# Pyro-Other.net
KiCad netlist of a schematic drawn in Altium Designer
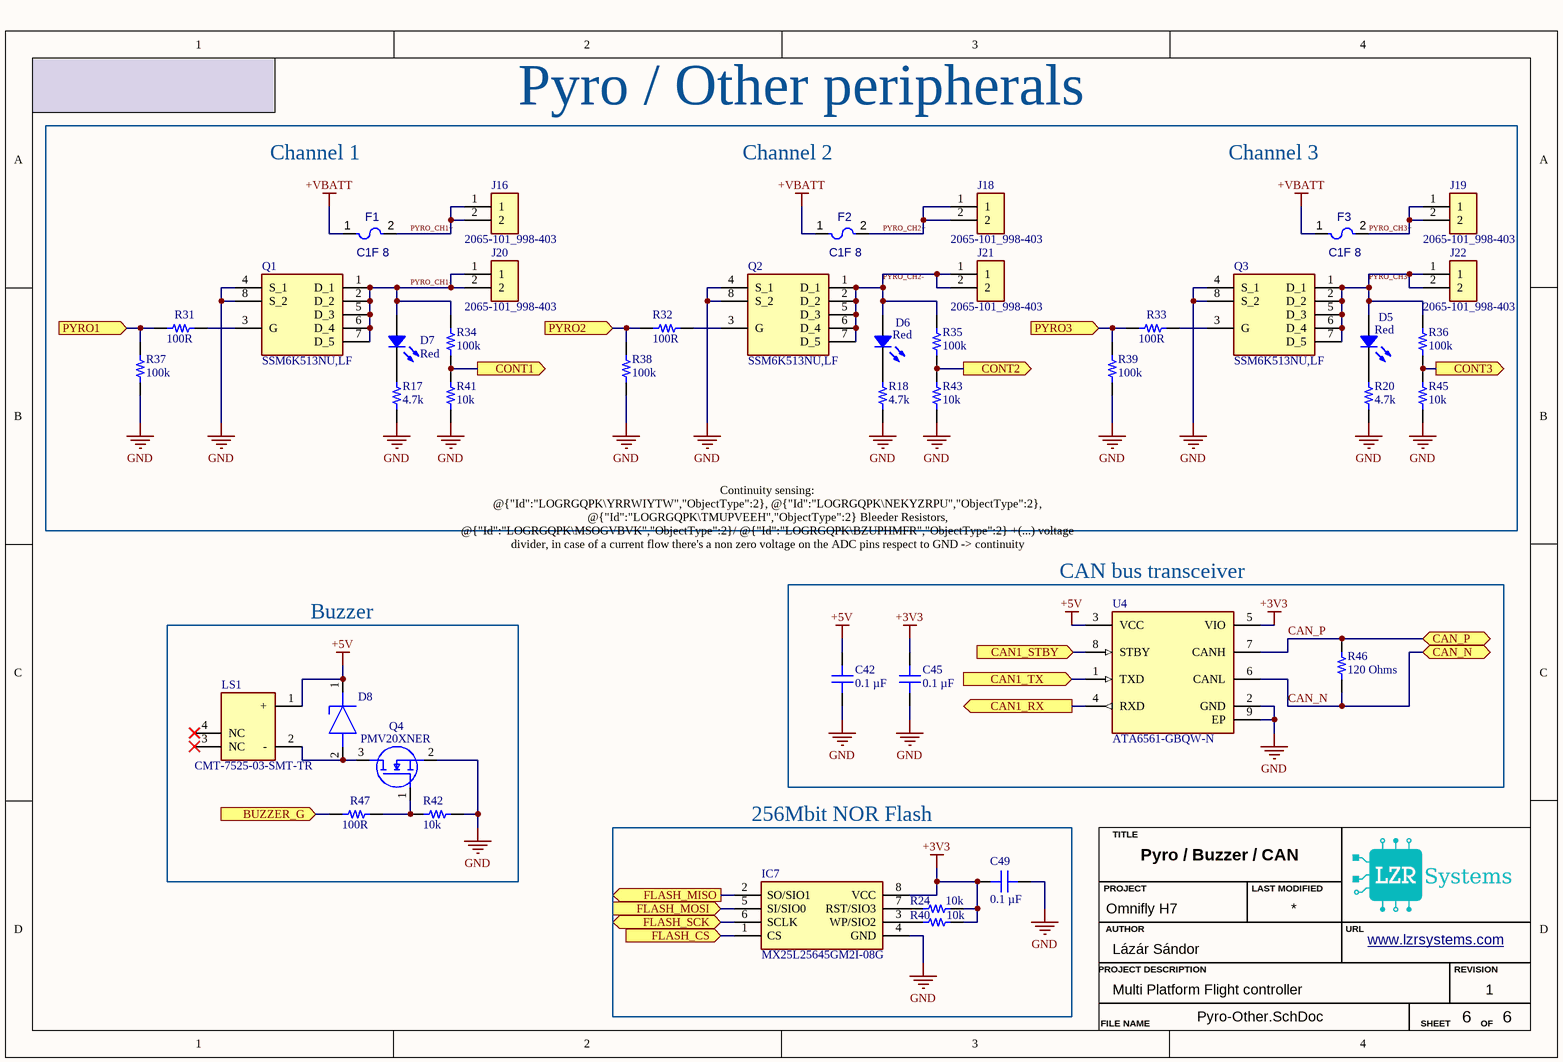
[diagram p0: Pyro-Other.SchDoc]

(export (version "E")
  (design (tool "Eeschema 10.0.6"))
  (components
    (comp (ref "C42")
      (value "0.1 µF")
      (footprint "MURATA GCM155 0402_1005")
      (description "CAP CER 0.1UF 50V X7R 0402")
      (fields
        (field (name "PART NUMBER") "GCM155R71H104ME02D")
        (field (name "CAPACITANCE") "0.1 µF")
        (field (name "MANUFACTURER") "Murata Electronics")
      )
      (libsource (lib "Celestial Altium Library - altium_library") (part "Capacitor"))
    )
    (comp (ref "C45")
      (value "0.1 µF")
      (footprint "MURATA GCM155 0402_1005")
      (description "CAP CER 0.1UF 50V X7R 0402")
      (fields
        (field (name "PART NUMBER") "GCM155R71H104ME02D")
        (field (name "CAPACITANCE") "0.1 µF")
        (field (name "MANUFACTURER") "Murata Electronics")
      )
      (libsource (lib "Celestial Altium Library - altium_library") (part "Capacitor"))
    )
    (comp (ref "C49")
      (value "0.1 µF")
      (footprint "MURATA GCM155 0402_1005")
      (description "CAP CER 0.1UF 50V X7R 0402")
      (fields
        (field (name "PART NUMBER") "GCM155R71H104ME02D")
        (field (name "CAPACITANCE") "0.1 µF")
        (field (name "MANUFACTURER") "Murata Electronics")
      )
      (libsource (lib "Celestial Altium Library - altium_library") (part "Capacitor"))
    )
    (comp (ref "D5")
      (value "Red")
      (footprint "LED 0402_1005 RED")
      (description "LED RED CLEAR 0402 SMD")
      (fields (field (name "PART NUMBER") "SM0402RC") (field (name "MANUFACTURER") "Bivar Inc."))
      (libsource (lib "Celestial Altium Library - altium_library") (part "LED"))
    )
    (comp (ref "D6")
      (value "Red")
      (footprint "LED 0402_1005 RED")
      (description "LED RED CLEAR 0402 SMD")
      (fields (field (name "PART NUMBER") "SM0402RC") (field (name "MANUFACTURER") "Bivar Inc."))
      (libsource (lib "Celestial Altium Library - altium_library") (part "LED"))
    )
    (comp (ref "D7")
      (value "Red")
      (footprint "LED 0402_1005 RED")
      (description "LED RED CLEAR 0402 SMD")
      (fields (field (name "PART NUMBER") "SM0402RC") (field (name "MANUFACTURER") "Bivar Inc."))
      (libsource (lib "Celestial Altium Library - altium_library") (part "LED"))
    )
    (comp (ref "D8")
      (value "PESD24VS1UA")
      (footprint "SamacSys:SOD2512X110N")
      (description "Diode ESD (Uni-directional)")
      (fields
        (field (name "MANUFACTURER_PART_NUMBER") "PESD24VS1UA,115")
        (field (name "MOUSER PART NUMBER") "771-PESD24VS1UA115")
      )
      (libsource (lib "*") (part "PESD24VS1UA,115"))
    )
    (comp (ref "F1")
      (value "C1F 8")
      (footprint "FP-3216FF-IPC_A")
      (description "Fuse Chip Fast Acting 10A 24V SMD Solder Pad 1206 T/R CSA/UL/cULus")
      (libsource (lib "Sandor Lazar") (part "FUSE-2"))
    )
    (comp (ref "F2")
      (value "C1F 8")
      (footprint "FP-3216FF-IPC_A")
      (description "Fuse Chip Fast Acting 10A 24V SMD Solder Pad 1206 T/R CSA/UL/cULus")
      (libsource (lib "Sandor Lazar") (part "FUSE-2"))
    )
    (comp (ref "F3")
      (value "C1F 8")
      (footprint "FP-3216FF-IPC_A")
      (description "Fuse Chip Fast Acting 10A 24V SMD Solder Pad 1206 T/R CSA/UL/cULus")
      (libsource (lib "Sandor Lazar") (part "FUSE-2"))
    )
    (comp (ref "IC7")
      (value "MX25L25645GM2I-08G")
      (footprint "SamacSys:SOIC127P790X216-8N")
      (description "Integrated Circuit")
      (libsource (lib "SamacSys") (part "MX25L25645GM2I-08G"))
    )
    (comp (ref "J16")
      (value "2065-101_998-403")
      (footprint "SamacSys:2065101998403")
      (description "Connector")
      (fields (field (name "MANUFACTURER_PART_NUMBER") "2065-101/998-403"))
      (libsource (lib "SamacSys") (part "2065-101_998-403"))
    )
    (comp (ref "J18")
      (value "2065-101_998-403")
      (footprint "SamacSys:2065101998403")
      (description "Connector")
      (fields (field (name "MANUFACTURER_PART_NUMBER") "2065-101/998-403"))
      (libsource (lib "SamacSys") (part "2065-101_998-403"))
    )
    (comp (ref "J19")
      (value "2065-101_998-403")
      (footprint "SamacSys:2065101998403")
      (description "Connector")
      (fields (field (name "MANUFACTURER_PART_NUMBER") "2065-101/998-403"))
      (libsource (lib "SamacSys") (part "2065-101_998-403"))
    )
    (comp (ref "J20")
      (value "2065-101_998-403")
      (footprint "SamacSys:2065101998403")
      (description "Connector")
      (fields (field (name "MANUFACTURER_PART_NUMBER") "2065-101/998-403"))
      (libsource (lib "SamacSys") (part "2065-101_998-403"))
    )
    (comp (ref "J21")
      (value "2065-101_998-403")
      (footprint "SamacSys:2065101998403")
      (description "Connector")
      (fields (field (name "MANUFACTURER_PART_NUMBER") "2065-101/998-403"))
      (libsource (lib "SamacSys") (part "2065-101_998-403"))
    )
    (comp (ref "J22")
      (value "2065-101_998-403")
      (footprint "SamacSys:2065101998403")
      (description "Connector")
      (fields (field (name "MANUFACTURER_PART_NUMBER") "2065-101/998-403"))
      (libsource (lib "SamacSys") (part "2065-101_998-403"))
    )
    (comp (ref "LS1")
      (value "CMT-7525-03-SMT-TR")
      (footprint "SamacSys:CMT752503SMTTR")
      (description "CMT-7525-03-SMT-TR - 7.5 mm")
      (fields (field (name "MOUSER PART NUMBER") "179-CMT-7525-03SMTTR"))
      (libsource (lib "SamacSys") (part "CMT-7525-03-SMT-TR"))
    )
    (comp (ref "Q1")
      (value "SSM6K513NU,LF")
      (footprint "SamacSys:SSM6K513NULF")
      (description "MOSFET (N-Channel)")
      (fields (field (name "MOUSER PART NUMBER") "757-SSM6K513NULF"))
      (libsource (lib "SamacSys") (part "SSM6K513NU,LF"))
    )
    (comp (ref "Q2")
      (value "SSM6K513NU,LF")
      (footprint "SamacSys:SSM6K513NULF")
      (description "MOSFET (N-Channel)")
      (fields (field (name "MOUSER PART NUMBER") "757-SSM6K513NULF"))
      (libsource (lib "SamacSys") (part "SSM6K513NU,LF"))
    )
    (comp (ref "Q3")
      (value "SSM6K513NU,LF")
      (footprint "SamacSys:SSM6K513NULF")
      (description "MOSFET (N-Channel)")
      (fields (field (name "MOUSER PART NUMBER") "757-SSM6K513NULF"))
      (libsource (lib "SamacSys") (part "SSM6K513NU,LF"))
    )
    (comp (ref "Q4")
      (value "PMV20XNER")
      (footprint "SamacSys:SOT95P230X110-3N")
      (description "MOSFET (N-Channel)")
      (fields (field (name "MOUSER PART NUMBER") "771-PMV20XNER"))
      (libsource (lib "SamacSys") (part "PMV20XNER"))
    )
    (comp (ref "R17")
      (value "4.7k")
      (footprint "YAGEO RES 0402_1005")
      (description "RES 4.7K OHM 1% 1/8W 0402")
      (fields (field (name "PART NUMBER") "AC0402FR-7W4K7L") (field (name "MANUFACTURER") "Yageo"))
      (libsource (lib "Celestial Altium Library - altium_library") (part "Resistor"))
    )
    (comp (ref "R18")
      (value "4.7k")
      (footprint "YAGEO RES 0402_1005")
      (description "RES 4.7K OHM 1% 1/8W 0402")
      (fields (field (name "PART NUMBER") "AC0402FR-7W4K7L") (field (name "MANUFACTURER") "Yageo"))
      (libsource (lib "Celestial Altium Library - altium_library") (part "Resistor"))
    )
    (comp (ref "R20")
      (value "4.7k")
      (footprint "YAGEO RES 0402_1005")
      (description "RES 4.7K OHM 1% 1/8W 0402")
      (fields (field (name "PART NUMBER") "AC0402FR-7W4K7L") (field (name "MANUFACTURER") "Yageo"))
      (libsource (lib "Celestial Altium Library - altium_library") (part "Resistor"))
    )
    (comp (ref "R24")
      (value "10k")
      (footprint "YAGEO RES 0402_1005")
      (description "RES 10K OHM 1% 1/16W 0402")
      (fields (field (name "PART NUMBER") "AC0402FR-1310KL") (field (name "MANUFACTURER") "Yageo"))
      (libsource (lib "Celestial Altium Library - altium_library") (part "Resistor"))
    )
    (comp (ref "R31")
      (value "100R")
      (footprint "RES 0402_1005")
      (description "RES SMD 100 OHM 1% 1/8W 0402")
      (fields
        (field (name "PART NUMBER") "504L1000FTNCFT")
        (field (name "MANUFACTURER") "American Technical Ceramics")
      )
      (libsource (lib "Celestial Altium Library - altium_library") (part "Resistor"))
    )
    (comp (ref "R32")
      (value "100R")
      (footprint "RES 0402_1005")
      (description "RES SMD 100 OHM 1% 1/8W 0402")
      (fields
        (field (name "PART NUMBER") "504L1000FTNCFT")
        (field (name "MANUFACTURER") "American Technical Ceramics")
      )
      (libsource (lib "Celestial Altium Library - altium_library") (part "Resistor"))
    )
    (comp (ref "R33")
      (value "100R")
      (footprint "RES 0402_1005")
      (description "RES SMD 100 OHM 1% 1/8W 0402")
      (fields
        (field (name "PART NUMBER") "504L1000FTNCFT")
        (field (name "MANUFACTURER") "American Technical Ceramics")
      )
      (libsource (lib "Celestial Altium Library - altium_library") (part "Resistor"))
    )
    (comp (ref "R34")
      (value "100k")
      (footprint "YAGEO RES 0402_1005")
      (description "RES 100K OHM 1% 1/16W 0402")
      (fields (field (name "PART NUMBER") "AC0402FR-13100KL") (field (name "MANUFACTURER") "Yageo"))
      (libsource (lib "Celestial Altium Library - altium_library") (part "Resistor"))
    )
    (comp (ref "R35")
      (value "100k")
      (footprint "YAGEO RES 0402_1005")
      (description "RES 100K OHM 1% 1/16W 0402")
      (fields (field (name "PART NUMBER") "AC0402FR-13100KL") (field (name "MANUFACTURER") "Yageo"))
      (libsource (lib "Celestial Altium Library - altium_library") (part "Resistor"))
    )
    (comp (ref "R36")
      (value "100k")
      (footprint "YAGEO RES 0402_1005")
      (description "RES 100K OHM 1% 1/16W 0402")
      (fields (field (name "PART NUMBER") "AC0402FR-13100KL") (field (name "MANUFACTURER") "Yageo"))
      (libsource (lib "Celestial Altium Library - altium_library") (part "Resistor"))
    )
    (comp (ref "R37")
      (value "100k")
      (footprint "YAGEO RES 0402_1005")
      (description "RES 100K OHM 1% 1/16W 0402")
      (fields (field (name "PART NUMBER") "AC0402FR-13100KL") (field (name "MANUFACTURER") "Yageo"))
      (libsource (lib "Celestial Altium Library - altium_library") (part "Resistor"))
    )
    (comp (ref "R38")
      (value "100k")
      (footprint "YAGEO RES 0402_1005")
      (description "RES 100K OHM 1% 1/16W 0402")
      (fields (field (name "PART NUMBER") "AC0402FR-13100KL") (field (name "MANUFACTURER") "Yageo"))
      (libsource (lib "Celestial Altium Library - altium_library") (part "Resistor"))
    )
    (comp (ref "R39")
      (value "100k")
      (footprint "YAGEO RES 0402_1005")
      (description "RES 100K OHM 1% 1/16W 0402")
      (fields (field (name "PART NUMBER") "AC0402FR-13100KL") (field (name "MANUFACTURER") "Yageo"))
      (libsource (lib "Celestial Altium Library - altium_library") (part "Resistor"))
    )
    (comp (ref "R40")
      (value "10k")
      (footprint "YAGEO RES 0402_1005")
      (description "RES 10K OHM 1% 1/16W 0402")
      (fields (field (name "PART NUMBER") "AC0402FR-1310KL") (field (name "MANUFACTURER") "Yageo"))
      (libsource (lib "Celestial Altium Library - altium_library") (part "Resistor"))
    )
    (comp (ref "R41")
      (value "10k")
      (footprint "YAGEO RES 0402_1005")
      (description "RES 10K OHM 1% 1/16W 0402")
      (fields (field (name "PART NUMBER") "AC0402FR-1310KL") (field (name "MANUFACTURER") "Yageo"))
      (libsource (lib "Celestial Altium Library - altium_library") (part "Resistor"))
    )
    (comp (ref "R42")
      (value "10k")
      (footprint "YAGEO RES 0402_1005")
      (description "RES 10K OHM 1% 1/16W 0402")
      (fields (field (name "PART NUMBER") "AC0402FR-1310KL") (field (name "MANUFACTURER") "Yageo"))
      (libsource (lib "Celestial Altium Library - altium_library") (part "Resistor"))
    )
    (comp (ref "R43")
      (value "10k")
      (footprint "YAGEO RES 0402_1005")
      (description "RES 10K OHM 1% 1/16W 0402")
      (fields (field (name "PART NUMBER") "AC0402FR-1310KL") (field (name "MANUFACTURER") "Yageo"))
      (libsource (lib "Celestial Altium Library - altium_library") (part "Resistor"))
    )
    (comp (ref "R45")
      (value "10k")
      (footprint "YAGEO RES 0402_1005")
      (description "RES 10K OHM 1% 1/16W 0402")
      (fields (field (name "PART NUMBER") "AC0402FR-1310KL") (field (name "MANUFACTURER") "Yageo"))
      (libsource (lib "Celestial Altium Library - altium_library") (part "Resistor"))
    )
    (comp (ref "R46")
      (value "120 Ohms")
      (footprint "KOA RES RK73 RN73 0603_1608")
      (description "RES 120 OHM 1% 1/8W 0603")
      (fields
        (field (name "PART NUMBER") "RK73H1JTTD1200F")
        (field (name "MANUFACTURER") "KOA Speer Electronics, Inc.")
      )
      (libsource (lib "Celestial Altium Library - altium_library") (part "Resistor"))
    )
    (comp (ref "R47")
      (value "100R")
      (footprint "RES 0402_1005")
      (description "RES SMD 100 OHM 1% 1/8W 0402")
      (fields
        (field (name "PART NUMBER") "504L1000FTNCFT")
        (field (name "MANUFACTURER") "American Technical Ceramics")
      )
      (libsource (lib "Celestial Altium Library - altium_library") (part "Resistor"))
    )
    (comp (ref "U4")
      (value "ATA6561-GBQW-N")
      (footprint "FP-C04-21358-IPC_B")
      (description "Industrial Grade Can Trx With Vio Pin (Dfn8) Rohs Compliant: Yes")
      (libsource (lib "Sandor Lazar") (part "3f00f5047d678022a67ce717b213c9e"))
    )
  )
  (nets
    (net (code "1") (name "+3V3") (class "Default")
      (node (ref "C45") (pin "1") (pinfunction "1_1") (pintype "passive"))
      (node (ref "C49") (pin "1") (pinfunction "1_1") (pintype "passive"))
      (node (ref "IC7") (pin "8") (pinfunction "VCC_8") (pintype "passive"))
      (node (ref "R24") (pin "1") (pinfunction "1_1") (pintype "passive"))
      (node (ref "R40") (pin "1") (pinfunction "1_1") (pintype "passive"))
      (node (ref "U4") (pin "5") (pinfunction "VIO_5") (pintype "passive"))
    )
    (net (code "2") (name "+5V") (class "Default")
      (node (ref "C42") (pin "1") (pinfunction "1_1") (pintype "passive"))
      (node (ref "D8") (pin "1") (pinfunction "K_1") (pintype "passive"))
      (node (ref "LS1") (pin "1") (pinfunction "+_1") (pintype "passive"))
      (node (ref "U4") (pin "3") (pinfunction "VCC_3") (pintype "power_in"))
    )
    (net (code "3") (name "+VBATT") (class "Default")
      (node (ref "F1") (pin "1") (pinfunction "1_1") (pintype "passive"))
      (node (ref "F2") (pin "1") (pinfunction "1_1") (pintype "passive"))
      (node (ref "F3") (pin "1") (pinfunction "1_1") (pintype "passive"))
    )
    (net (code "4") (name "/BUZZER_G") (class "Default")
      (node (ref "R47") (pin "1") (pinfunction "1_1") (pintype "passive"))
    )
    (net (code "5") (name "/CAN1_RX") (class "Default")
      (node (ref "U4") (pin "4") (pinfunction "RXD_4") (pintype "output"))
    )
    (net (code "6") (name "/CAN1_STBY") (class "Default")
      (node (ref "U4") (pin "8") (pinfunction "STBY_8") (pintype "input"))
    )
    (net (code "7") (name "/CAN1_TX") (class "Default")
      (node (ref "U4") (pin "1") (pinfunction "TXD_1") (pintype "input"))
    )
    (net (code "8") (name "/CAN_N") (class "Default")
      (node (ref "R46") (pin "1") (pinfunction "1_1") (pintype "passive"))
      (node (ref "U4") (pin "6") (pinfunction "CANL_6") (pintype "passive"))
    )
    (net (code "9") (name "/CAN_P") (class "Default")
      (node (ref "R46") (pin "2") (pinfunction "2_2") (pintype "passive"))
      (node (ref "U4") (pin "7") (pinfunction "CANH_7") (pintype "passive"))
    )
    (net (code "10") (name "/CONT1") (class "Default")
      (node (ref "R34") (pin "1") (pinfunction "1_1") (pintype "passive"))
      (node (ref "R41") (pin "2") (pinfunction "2_2") (pintype "passive"))
    )
    (net (code "11") (name "/CONT2") (class "Default")
      (node (ref "R35") (pin "1") (pinfunction "1_1") (pintype "passive"))
      (node (ref "R43") (pin "2") (pinfunction "2_2") (pintype "passive"))
    )
    (net (code "12") (name "/CONT3") (class "Default")
      (node (ref "R36") (pin "1") (pinfunction "1_1") (pintype "passive"))
      (node (ref "R45") (pin "2") (pinfunction "2_2") (pintype "passive"))
    )
    (net (code "13") (name "/FLASH_CS") (class "Default")
      (node (ref "IC7") (pin "1") (pinfunction "CS_1") (pintype "passive"))
    )
    (net (code "14") (name "/FLASH_MISO") (class "Default")
      (node (ref "IC7") (pin "2") (pinfunction "SO/SIO1_2") (pintype "passive"))
    )
    (net (code "15") (name "/FLASH_MOSI") (class "Default")
      (node (ref "IC7") (pin "5") (pinfunction "SI/SIO0_5") (pintype "passive"))
    )
    (net (code "16") (name "/FLASH_SCK") (class "Default")
      (node (ref "IC7") (pin "6") (pinfunction "SCLK_6") (pintype "passive"))
    )
    (net (code "17") (name "/PYRO1") (class "Default")
      (node (ref "R31") (pin "1") (pinfunction "1_1") (pintype "passive"))
      (node (ref "R37") (pin "2") (pinfunction "2_2") (pintype "passive"))
    )
    (net (code "18") (name "/PYRO2") (class "Default")
      (node (ref "R32") (pin "1") (pinfunction "1_1") (pintype "passive"))
      (node (ref "R38") (pin "2") (pinfunction "2_2") (pintype "passive"))
    )
    (net (code "19") (name "/PYRO3") (class "Default")
      (node (ref "R33") (pin "1") (pinfunction "1_1") (pintype "passive"))
      (node (ref "R39") (pin "2") (pinfunction "2_2") (pintype "passive"))
    )
    (net (code "20") (name "/PYRO_CH1+") (class "Default")
      (node (ref "F1") (pin "2") (pinfunction "2_2") (pintype "passive"))
      (node (ref "J16") (pin "1") (pinfunction "1_1") (pintype "passive"))
      (node (ref "J16") (pin "2") (pinfunction "2_2") (pintype "passive"))
    )
    (net (code "21") (name "/PYRO_CH1-") (class "Default")
      (node (ref "D7") (pin "1") (pinfunction "1_1") (pintype "passive"))
      (node (ref "J20") (pin "1") (pinfunction "1_1") (pintype "passive"))
      (node (ref "J20") (pin "2") (pinfunction "2_2") (pintype "passive"))
      (node (ref "Q1") (pin "1") (pinfunction "D_1_1") (pintype "passive"))
      (node (ref "Q1") (pin "2") (pinfunction "D_2_2") (pintype "passive"))
      (node (ref "Q1") (pin "5") (pinfunction "D_3_5") (pintype "passive"))
      (node (ref "Q1") (pin "6") (pinfunction "D_4_6") (pintype "passive"))
      (node (ref "Q1") (pin "7") (pinfunction "D_5_7") (pintype "passive"))
      (node (ref "R34") (pin "2") (pinfunction "2_2") (pintype "passive"))
    )
    (net (code "22") (name "/PYRO_CH2+") (class "Default")
      (node (ref "F2") (pin "2") (pinfunction "2_2") (pintype "passive"))
      (node (ref "J18") (pin "1") (pinfunction "1_1") (pintype "passive"))
      (node (ref "J18") (pin "2") (pinfunction "2_2") (pintype "passive"))
    )
    (net (code "23") (name "/PYRO_CH2-") (class "Default")
      (node (ref "D6") (pin "1") (pinfunction "1_1") (pintype "passive"))
      (node (ref "J21") (pin "1") (pinfunction "1_1") (pintype "passive"))
      (node (ref "J21") (pin "2") (pinfunction "2_2") (pintype "passive"))
      (node (ref "Q2") (pin "1") (pinfunction "D_1_1") (pintype "passive"))
      (node (ref "Q2") (pin "2") (pinfunction "D_2_2") (pintype "passive"))
      (node (ref "Q2") (pin "5") (pinfunction "D_3_5") (pintype "passive"))
      (node (ref "Q2") (pin "6") (pinfunction "D_4_6") (pintype "passive"))
      (node (ref "Q2") (pin "7") (pinfunction "D_5_7") (pintype "passive"))
      (node (ref "R35") (pin "2") (pinfunction "2_2") (pintype "passive"))
    )
    (net (code "24") (name "/PYRO_CH3+") (class "Default")
      (node (ref "F3") (pin "2") (pinfunction "2_2") (pintype "passive"))
      (node (ref "J19") (pin "1") (pinfunction "1_1") (pintype "passive"))
      (node (ref "J19") (pin "2") (pinfunction "2_2") (pintype "passive"))
    )
    (net (code "25") (name "/PYRO_CH3-") (class "Default")
      (node (ref "D5") (pin "1") (pinfunction "1_1") (pintype "passive"))
      (node (ref "J22") (pin "1") (pinfunction "1_1") (pintype "passive"))
      (node (ref "J22") (pin "2") (pinfunction "2_2") (pintype "passive"))
      (node (ref "Q3") (pin "1") (pinfunction "D_1_1") (pintype "passive"))
      (node (ref "Q3") (pin "2") (pinfunction "D_2_2") (pintype "passive"))
      (node (ref "Q3") (pin "5") (pinfunction "D_3_5") (pintype "passive"))
      (node (ref "Q3") (pin "6") (pinfunction "D_4_6") (pintype "passive"))
      (node (ref "Q3") (pin "7") (pinfunction "D_5_7") (pintype "passive"))
      (node (ref "R36") (pin "2") (pinfunction "2_2") (pintype "passive"))
    )
    (net (code "26") (name "GND") (class "Default")
      (node (ref "C42") (pin "2") (pinfunction "2_2") (pintype "passive"))
      (node (ref "C45") (pin "2") (pinfunction "2_2") (pintype "passive"))
      (node (ref "C49") (pin "2") (pinfunction "2_2") (pintype "passive"))
      (node (ref "IC7") (pin "4") (pinfunction "GND_4") (pintype "passive"))
      (node (ref "Q1") (pin "4") (pinfunction "S_1_4") (pintype "passive"))
      (node (ref "Q1") (pin "8") (pinfunction "S_2_8") (pintype "passive"))
      (node (ref "Q2") (pin "4") (pinfunction "S_1_4") (pintype "passive"))
      (node (ref "Q2") (pin "8") (pinfunction "S_2_8") (pintype "passive"))
      (node (ref "Q3") (pin "4") (pinfunction "S_1_4") (pintype "passive"))
      (node (ref "Q3") (pin "8") (pinfunction "S_2_8") (pintype "passive"))
      (node (ref "Q4") (pin "2") (pinfunction "S_2") (pintype "passive"))
      (node (ref "R17") (pin "1") (pinfunction "1_1") (pintype "passive"))
      (node (ref "R18") (pin "1") (pinfunction "1_1") (pintype "passive"))
      (node (ref "R20") (pin "1") (pinfunction "1_1") (pintype "passive"))
      (node (ref "R37") (pin "1") (pinfunction "1_1") (pintype "passive"))
      (node (ref "R38") (pin "1") (pinfunction "1_1") (pintype "passive"))
      (node (ref "R39") (pin "1") (pinfunction "1_1") (pintype "passive"))
      (node (ref "R41") (pin "1") (pinfunction "1_1") (pintype "passive"))
      (node (ref "R42") (pin "1") (pinfunction "1_1") (pintype "passive"))
      (node (ref "R43") (pin "1") (pinfunction "1_1") (pintype "passive"))
      (node (ref "R45") (pin "1") (pinfunction "1_1") (pintype "passive"))
      (node (ref "U4") (pin "2") (pinfunction "GND_2") (pintype "power_in"))
      (node (ref "U4") (pin "9") (pinfunction "EP_9") (pintype "power_in"))
    )
    (net (code "27") (name "Net-(D5-Pad2)") (class "Default")
      (node (ref "D5") (pin "2") (pinfunction "2_2") (pintype "passive"))
      (node (ref "R20") (pin "2") (pinfunction "2_2") (pintype "passive"))
    )
    (net (code "28") (name "Net-(D6-Pad2)") (class "Default")
      (node (ref "D6") (pin "2") (pinfunction "2_2") (pintype "passive"))
      (node (ref "R18") (pin "2") (pinfunction "2_2") (pintype "passive"))
    )
    (net (code "29") (name "Net-(D7-Pad2)") (class "Default")
      (node (ref "D7") (pin "2") (pinfunction "2_2") (pintype "passive"))
      (node (ref "R17") (pin "2") (pinfunction "2_2") (pintype "passive"))
    )
    (net (code "30") (name "Net-(D8-A)") (class "Default")
      (node (ref "D8") (pin "2") (pinfunction "A_2") (pintype "passive"))
      (node (ref "LS1") (pin "2") (pinfunction "-_2") (pintype "passive"))
      (node (ref "Q4") (pin "3") (pinfunction "D_3") (pintype "passive"))
    )
    (net (code "31") (name "Net-(IC7-RST{slash}SIO3)") (class "Default")
      (node (ref "IC7") (pin "7") (pinfunction "RST/SIO3_7") (pintype "passive"))
      (node (ref "R24") (pin "2") (pinfunction "2_2") (pintype "passive"))
    )
    (net (code "32") (name "Net-(IC7-WP{slash}SIO2)") (class "Default")
      (node (ref "IC7") (pin "3") (pinfunction "WP/SIO2_3") (pintype "passive"))
      (node (ref "R40") (pin "2") (pinfunction "2_2") (pintype "passive"))
    )
    (net (code "33") (name "Net-(Q1-G)") (class "Default")
      (node (ref "Q1") (pin "3") (pinfunction "G_3") (pintype "passive"))
      (node (ref "R31") (pin "2") (pinfunction "2_2") (pintype "passive"))
    )
    (net (code "34") (name "Net-(Q2-G)") (class "Default")
      (node (ref "Q2") (pin "3") (pinfunction "G_3") (pintype "passive"))
      (node (ref "R32") (pin "2") (pinfunction "2_2") (pintype "passive"))
    )
    (net (code "35") (name "Net-(Q3-G)") (class "Default")
      (node (ref "Q3") (pin "3") (pinfunction "G_3") (pintype "passive"))
      (node (ref "R33") (pin "2") (pinfunction "2_2") (pintype "passive"))
    )
    (net (code "36") (name "Net-(Q4-G)") (class "Default")
      (node (ref "Q4") (pin "1") (pinfunction "G_1") (pintype "passive"))
      (node (ref "R42") (pin "2") (pinfunction "2_2") (pintype "passive"))
      (node (ref "R47") (pin "2") (pinfunction "2_2") (pintype "passive"))
    )
    (net (code "37") (name "unconnected-(LS1-NC-Pad3)") (class "Default")
      (node (ref "LS1") (pin "3") (pinfunction "NC_3") (pintype "passive+no_connect"))
    )
    (net (code "38") (name "unconnected-(LS1-NC-Pad4)") (class "Default")
      (node (ref "LS1") (pin "4") (pinfunction "NC_4") (pintype "passive+no_connect"))
    )
  )
)
